# 009pcb4_12mil.net
KiCad netlist of a schematic drawn in EAGLE
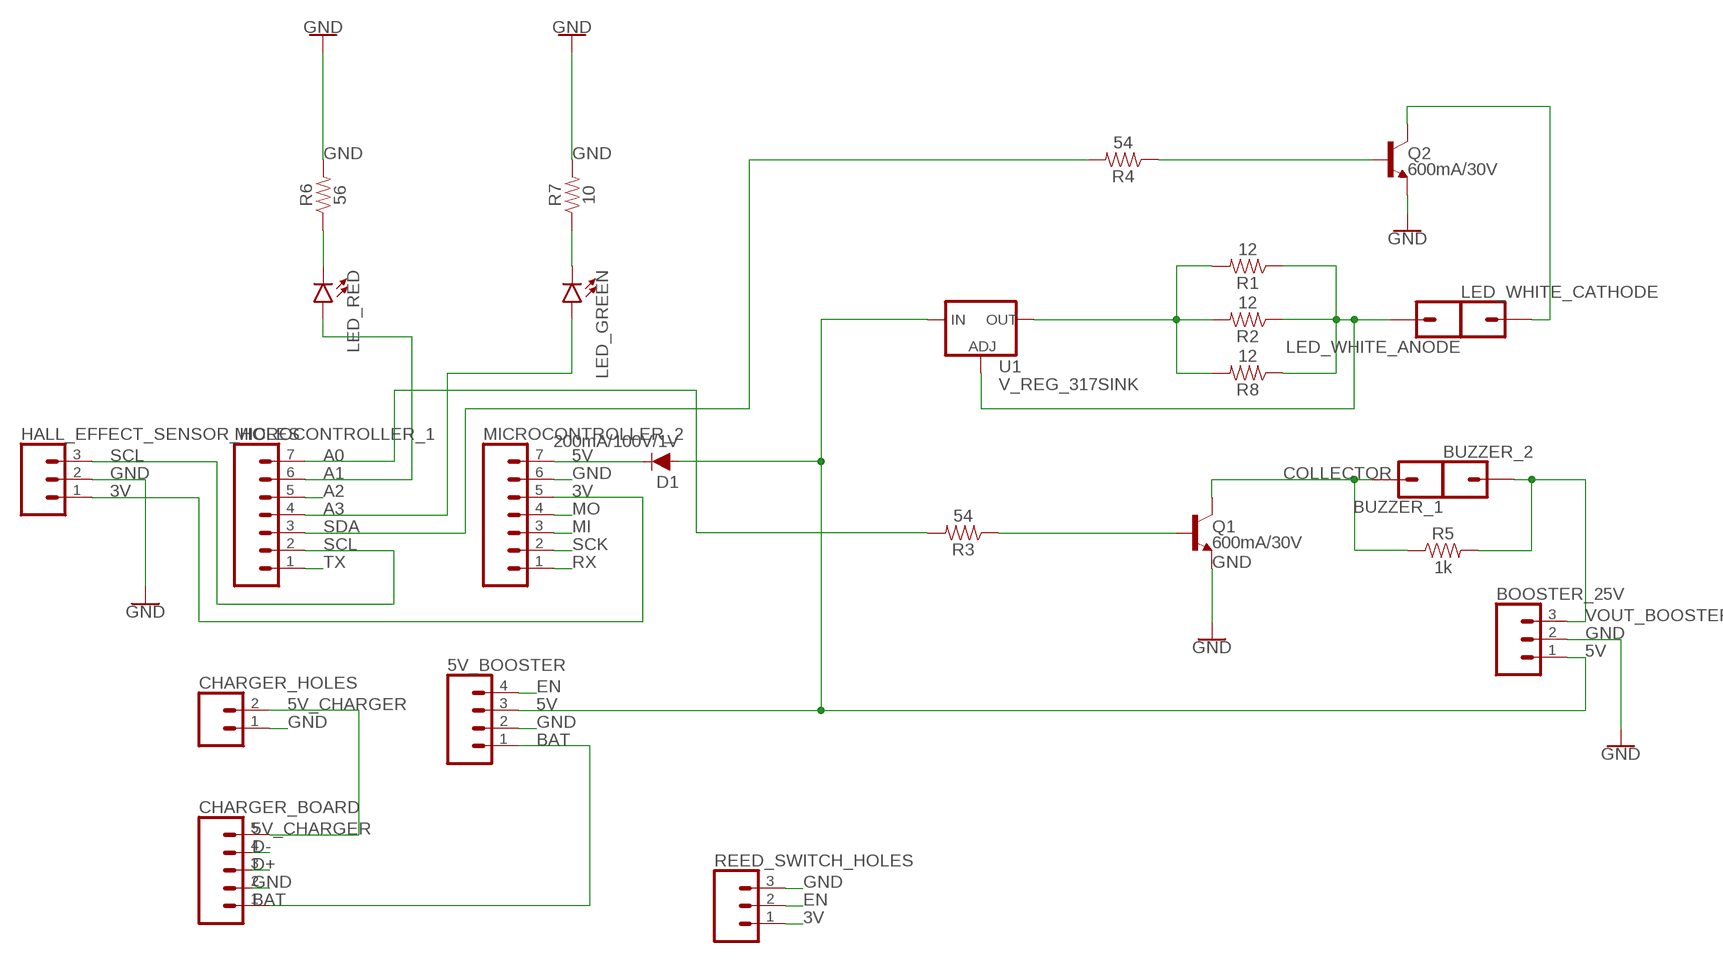
[diagram p0: schematic, sheet 1]

(export (version "E")
  (design (tool "Eeschema 10.0.6"))
  (components
    (comp (ref "5V_BOOSTER")
      (value "CONN_04")
      (footprint "eagle-import:1X04")
      (libsource (lib "eagle-import") (part "CONN_04"))
    )
    (comp (ref "BOOSTER_25V")
      (value "CONN_03")
      (footprint "eagle-import:1X03")
      (libsource (lib "eagle-import") (part "CONN_03"))
    )
    (comp (ref "BUZZER_1")
      (value "CONN_01")
      (footprint "eagle-import:1X01")
      (libsource (lib "eagle-import") (part "CONN_01"))
    )
    (comp (ref "BUZZER_2")
      (value "CONN_01")
      (footprint "eagle-import:1X01")
      (libsource (lib "eagle-import") (part "CONN_01"))
    )
    (comp (ref "CHARGER_BOARD")
      (value "CONN_05")
      (footprint "eagle-import:1X05")
      (libsource (lib "eagle-import") (part "CONN_05"))
    )
    (comp (ref "CHARGER_HOLES")
      (value "CONN_02")
      (footprint "eagle-import:1X02")
      (libsource (lib "eagle-import") (part "CONN_02"))
    )
    (comp (ref "D1")
      (value "200mA/100V/1V")
      (footprint "eagle-import:DIODE-1N4148")
      (libsource (lib "eagle-import") (part "DIODE-1N4148"))
    )
    (comp (ref "HALL_EFFECT_SENSOR_HOLES")
      (value "CONN_03")
      (footprint "eagle-import:1X03")
      (libsource (lib "eagle-import") (part "CONN_03"))
    )
    (comp (ref "LED_GREEN")
      (value "LED5MM")
      (footprint "eagle-import:LED_5MM")
      (libsource (lib "eagle-import") (part "LED5MM"))
    )
    (comp (ref "LED_RED")
      (value "LED5MM")
      (footprint "eagle-import:LED_5MM")
      (libsource (lib "eagle-import") (part "LED5MM"))
    )
    (comp (ref "LED_WHITE_ANODE")
      (value "CONN_01")
      (footprint "eagle-import:1X01")
      (libsource (lib "eagle-import") (part "CONN_01"))
    )
    (comp (ref "LED_WHITE_CATHODE")
      (value "CONN_01")
      (footprint "eagle-import:1X01")
      (libsource (lib "eagle-import") (part "CONN_01"))
    )
    (comp (ref "MICROCONTROLLER_1")
      (value "CONN_07")
      (footprint "eagle-import:1X07")
      (libsource (lib "eagle-import") (part "CONN_07"))
    )
    (comp (ref "MICROCONTROLLER_2")
      (value "CONN_07")
      (footprint "eagle-import:1X07")
      (libsource (lib "eagle-import") (part "CONN_07"))
    )
    (comp (ref "Q1")
      (value "600mA/30V")
      (footprint "eagle-import:TO-92")
      (libsource (lib "eagle-import") (part "TRANS_NPN-2N3904"))
    )
    (comp (ref "Q2")
      (value "600mA/30V")
      (footprint "eagle-import:TO-92")
      (libsource (lib "eagle-import") (part "TRANS_NPN-2N3904"))
    )
    (comp (ref "R1")
      (value "12")
      (footprint "eagle-import:AXIAL-0.3")
      (libsource (lib "eagle-import") (part "10OHM-HORIZ-1/4W-1%"))
    )
    (comp (ref "R2")
      (value "12")
      (footprint "eagle-import:AXIAL-0.3")
      (libsource (lib "eagle-import") (part "10OHM-HORIZ-1/4W-1%"))
    )
    (comp (ref "R3")
      (value "54")
      (footprint "eagle-import:AXIAL-0.3")
      (libsource (lib "eagle-import") (part "10OHM-HORIZ-1/4W-1%"))
    )
    (comp (ref "R4")
      (value "54")
      (footprint "eagle-import:AXIAL-0.3")
      (libsource (lib "eagle-import") (part "10OHM-HORIZ-1/4W-1%"))
    )
    (comp (ref "R5")
      (value "1k")
      (footprint "eagle-import:AXIAL-0.3")
      (libsource (lib "eagle-import") (part "1KOHM-HORIZ-1/4W-1%"))
    )
    (comp (ref "R6")
      (value "56")
      (footprint "eagle-import:AXIAL-0.3")
      (libsource (lib "eagle-import") (part "10OHM-HORIZ-1/4W-1%"))
    )
    (comp (ref "R7")
      (value "10")
      (footprint "eagle-import:AXIAL-0.3")
      (libsource (lib "eagle-import") (part "10OHM-HORIZ-1/4W-1%"))
    )
    (comp (ref "R8")
      (value "12")
      (footprint "eagle-import:AXIAL-0.3")
      (libsource (lib "eagle-import") (part "10OHM-HORIZ-1/4W-1%"))
    )
    (comp (ref "REED_SWITCH_HOLES")
      (value "CONN_03")
      (footprint "eagle-import:1X03")
      (libsource (lib "eagle-import") (part "CONN_03"))
    )
    (comp (ref "U1")
      (value "V_REG_317SINK")
      (footprint "eagle-import:TO220-ADJ")
      (libsource (lib "eagle-import") (part "V_REG_317SINK"))
    )
  )
  (nets
    (net (code "1") (name "/3V") (class "Default")
      (node (ref "HALL_EFFECT_SENSOR_HOLES") (pin "1") (pinfunction "1_1") (pintype "passive"))
      (node (ref "MICROCONTROLLER_2") (pin "5") (pinfunction "5_5") (pintype "passive"))
      (node (ref "REED_SWITCH_HOLES") (pin "1") (pinfunction "1_1") (pintype "passive"))
    )
    (net (code "2") (name "/5V") (class "Default")
      (node (ref "5V_BOOSTER") (pin "3") (pinfunction "3_3") (pintype "passive"))
      (node (ref "BOOSTER_25V") (pin "1") (pinfunction "1_1") (pintype "passive"))
      (node (ref "D1") (pin "A") (pinfunction "A_A") (pintype "passive"))
      (node (ref "U1") (pin "IN") (pinfunction "IN_IN") (pintype "input"))
    )
    (net (code "3") (name "/5V_CHARGER") (class "Default")
      (node (ref "CHARGER_BOARD") (pin "5") (pinfunction "5_5") (pintype "passive"))
      (node (ref "CHARGER_HOLES") (pin "2") (pinfunction "2_2") (pintype "passive"))
    )
    (net (code "4") (name "/A0") (class "Default")
      (node (ref "MICROCONTROLLER_1") (pin "7") (pinfunction "7_7") (pintype "passive"))
      (node (ref "R3") (pin "P$2") (pinfunction "2_P$2") (pintype "passive"))
    )
    (net (code "5") (name "/A1") (class "Default")
      (node (ref "LED_RED") (pin "A") (pinfunction "A_A") (pintype "passive"))
      (node (ref "MICROCONTROLLER_1") (pin "6") (pinfunction "6_6") (pintype "passive"))
    )
    (net (code "6") (name "/A2") (class "Default")
      (node (ref "MICROCONTROLLER_1") (pin "5") (pinfunction "5_5") (pintype "passive"))
    )
    (net (code "7") (name "/A3") (class "Default")
      (node (ref "LED_GREEN") (pin "A") (pinfunction "A_A") (pintype "passive"))
      (node (ref "MICROCONTROLLER_1") (pin "4") (pinfunction "4_4") (pintype "passive"))
    )
    (net (code "8") (name "/BASE") (class "Default")
      (node (ref "Q1") (pin "2") (pinfunction "B_2") (pintype "passive"))
      (node (ref "Q2") (pin "2") (pinfunction "B_2") (pintype "passive"))
      (node (ref "R3") (pin "P$1") (pinfunction "1_P$1") (pintype "passive"))
      (node (ref "R4") (pin "P$1") (pinfunction "1_P$1") (pintype "passive"))
    )
    (net (code "9") (name "/BAT") (class "Default")
      (node (ref "5V_BOOSTER") (pin "1") (pinfunction "1_1") (pintype "passive"))
      (node (ref "CHARGER_BOARD") (pin "1") (pinfunction "1_1") (pintype "passive"))
    )
    (net (code "10") (name "/COLLECTOR") (class "Default")
      (node (ref "BUZZER_1") (pin "1") (pinfunction "1_1") (pintype "passive"))
      (node (ref "LED_WHITE_CATHODE") (pin "1") (pinfunction "1_1") (pintype "passive"))
      (node (ref "Q1") (pin "3") (pinfunction "C_3") (pintype "passive"))
      (node (ref "Q2") (pin "3") (pinfunction "C_3") (pintype "passive"))
      (node (ref "R5") (pin "P$1") (pinfunction "1_P$1") (pintype "passive"))
    )
    (net (code "11") (name "/D+") (class "Default")
      (node (ref "CHARGER_BOARD") (pin "3") (pinfunction "3_3") (pintype "passive"))
    )
    (net (code "12") (name "/D-") (class "Default")
      (node (ref "CHARGER_BOARD") (pin "4") (pinfunction "4_4") (pintype "passive"))
    )
    (net (code "13") (name "/EN") (class "Default")
      (node (ref "5V_BOOSTER") (pin "4") (pinfunction "4_4") (pintype "passive"))
      (node (ref "REED_SWITCH_HOLES") (pin "2") (pinfunction "2_2") (pintype "passive"))
    )
    (net (code "14") (name "/MI") (class "Default")
      (node (ref "MICROCONTROLLER_2") (pin "3") (pinfunction "3_3") (pintype "passive"))
    )
    (net (code "15") (name "/MO") (class "Default")
      (node (ref "MICROCONTROLLER_2") (pin "4") (pinfunction "4_4") (pintype "passive"))
    )
    (net (code "16") (name "/RX") (class "Default")
      (node (ref "MICROCONTROLLER_2") (pin "1") (pinfunction "1_1") (pintype "passive"))
    )
    (net (code "17") (name "/SCK") (class "Default")
      (node (ref "MICROCONTROLLER_2") (pin "2") (pinfunction "2_2") (pintype "passive"))
    )
    (net (code "18") (name "/SCL") (class "Default")
      (node (ref "HALL_EFFECT_SENSOR_HOLES") (pin "3") (pinfunction "3_3") (pintype "passive"))
      (node (ref "MICROCONTROLLER_1") (pin "2") (pinfunction "2_2") (pintype "passive"))
    )
    (net (code "19") (name "/SDA") (class "Default")
      (node (ref "MICROCONTROLLER_1") (pin "3") (pinfunction "3_3") (pintype "passive"))
      (node (ref "R4") (pin "P$2") (pinfunction "2_P$2") (pintype "passive"))
    )
    (net (code "20") (name "/TX") (class "Default")
      (node (ref "MICROCONTROLLER_1") (pin "1") (pinfunction "1_1") (pintype "passive"))
    )
    (net (code "21") (name "/VOUT_BOOSTER") (class "Default")
      (node (ref "BOOSTER_25V") (pin "3") (pinfunction "3_3") (pintype "passive"))
      (node (ref "BUZZER_2") (pin "1") (pinfunction "1_1") (pintype "passive"))
      (node (ref "R5") (pin "P$2") (pinfunction "2_P$2") (pintype "passive"))
    )
    (net (code "22") (name "GND") (class "Default")
      (node (ref "5V_BOOSTER") (pin "2") (pinfunction "2_2") (pintype "passive"))
      (node (ref "BOOSTER_25V") (pin "2") (pinfunction "2_2") (pintype "passive"))
      (node (ref "CHARGER_BOARD") (pin "2") (pinfunction "2_2") (pintype "passive"))
      (node (ref "CHARGER_HOLES") (pin "1") (pinfunction "1_1") (pintype "passive"))
      (node (ref "HALL_EFFECT_SENSOR_HOLES") (pin "2") (pinfunction "2_2") (pintype "passive"))
      (node (ref "MICROCONTROLLER_2") (pin "6") (pinfunction "6_6") (pintype "passive"))
      (node (ref "Q1") (pin "1") (pinfunction "E_1") (pintype "passive"))
      (node (ref "Q2") (pin "1") (pinfunction "E_1") (pintype "passive"))
      (node (ref "R6") (pin "P$2") (pinfunction "2_P$2") (pintype "passive"))
      (node (ref "R7") (pin "P$2") (pinfunction "2_P$2") (pintype "passive"))
      (node (ref "REED_SWITCH_HOLES") (pin "3") (pinfunction "3_3") (pintype "passive"))
    )
    (net (code "23") (name "Net-(D1-PadC)") (class "Default")
      (node (ref "D1") (pin "C") (pinfunction "C_C") (pintype "passive"))
      (node (ref "MICROCONTROLLER_2") (pin "7") (pinfunction "7_7") (pintype "passive"))
    )
    (net (code "24") (name "Net-(LED_GREEN-C)") (class "Default")
      (node (ref "LED_GREEN") (pin "K") (pinfunction "C_K") (pintype "passive"))
      (node (ref "R7") (pin "P$1") (pinfunction "1_P$1") (pintype "passive"))
    )
    (net (code "25") (name "Net-(LED_RED-C)") (class "Default")
      (node (ref "LED_RED") (pin "K") (pinfunction "C_K") (pintype "passive"))
      (node (ref "R6") (pin "P$1") (pinfunction "1_P$1") (pintype "passive"))
    )
    (net (code "26") (name "Net-(R1-1)") (class "Default")
      (node (ref "LED_WHITE_ANODE") (pin "1") (pinfunction "1_1") (pintype "passive"))
      (node (ref "R1") (pin "P$1") (pinfunction "1_P$1") (pintype "passive"))
      (node (ref "R2") (pin "P$1") (pinfunction "1_P$1") (pintype "passive"))
      (node (ref "R8") (pin "P$1") (pinfunction "1_P$1") (pintype "passive"))
      (node (ref "U1") (pin "ADJ") (pinfunction "ADJ_ADJ") (pintype "input"))
    )
    (net (code "27") (name "Net-(R1-2)") (class "Default")
      (node (ref "R1") (pin "P$2") (pinfunction "2_P$2") (pintype "passive"))
      (node (ref "R2") (pin "P$2") (pinfunction "2_P$2") (pintype "passive"))
      (node (ref "R8") (pin "P$2") (pinfunction "2_P$2") (pintype "passive"))
      (node (ref "U1") (pin "OUT") (pinfunction "OUT_OUT") (pintype "output"))
    )
  )
)
